# t6713_v_1_0.net
KiCad netlist of a schematic drawn in EAGLE
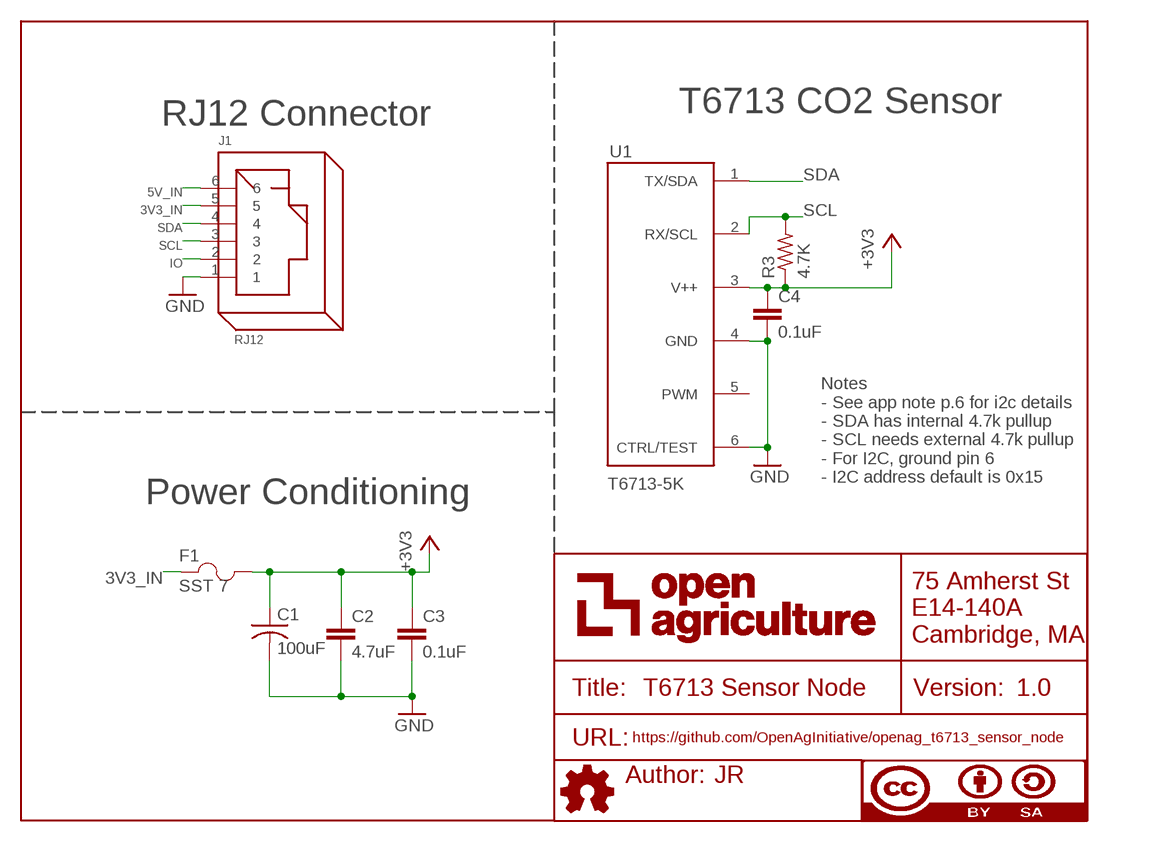
[diagram p0: schematic, sheet 1]

(export (version "E")
  (design (tool "Eeschema 10.0.6"))
  (components
    (comp (ref "C1")
      (value "100uF")
      (footprint "eagle-import:EEE-1HA101UP")
      (libsource (lib "eagle-import") (part "100UF-EEE-1HA101UP"))
    )
    (comp (ref "C2")
      (value "4.7uF")
      (footprint "eagle-import:C0805")
      (libsource (lib "eagle-import") (part "4.7UF-CL21A475KBQNNNE"))
    )
    (comp (ref "C3")
      (value "0.1uF")
      (footprint "eagle-import:C0603")
      (libsource (lib "eagle-import") (part "0.1UF-C0603C104K5RACTU"))
    )
    (comp (ref "C4")
      (value "0.1uF")
      (footprint "eagle-import:C0603")
      (libsource (lib "eagle-import") (part "0.1UF-C0603C104K5RACTU"))
    )
    (comp (ref "F1")
      (value "SST 7")
      (footprint "eagle-import:SS")
      (libsource (lib "eagle-import") (part "SST_7"))
    )
    (comp (ref "FRAME1")
      (value "DOCFIELD")
      (footprint "eagle-import:DOCFIELD")
      (fields
        (field (name "AUTHOR") "JR")
        (field (name "TITLE") "T6713 Sensor Node")
        (field (name "URL") "https://github.com/OpenAgInitiative/openag_t6713_sensor_node")
      )
      (libsource (lib "eagle-import") (part "DOCFIELD"))
    )
    (comp (ref "J1")
      (value "RJ12")
      (footprint "eagle-import:RJ12")
      (libsource (lib "eagle-import") (part "A-2004-1-4-LP-N-R"))
    )
    (comp (ref "R3")
      (value "4.7K")
      (footprint "eagle-import:R1206")
      (libsource (lib "eagle-import") (part "4.7K-RC1206JR-074K7L"))
    )
    (comp (ref "U1")
      (value "T6713-5K")
      (footprint "eagle-import:T6713")
      (libsource (lib "eagle-import") (part "T6713-5K"))
    )
  )
  (nets
    (net (code "1") (name "+3V3") (class "Default")
      (node (ref "C1") (pin "+") (pinfunction "1(+)_+") (pintype "passive"))
      (node (ref "C2") (pin "1") (pinfunction "1_1") (pintype "passive"))
      (node (ref "C3") (pin "1") (pinfunction "1_1") (pintype "passive"))
      (node (ref "C4") (pin "1") (pinfunction "1_1") (pintype "passive"))
      (node (ref "F1") (pin "2") (pinfunction "2_2") (pintype "passive"))
      (node (ref "R3") (pin "1") (pinfunction "1_1") (pintype "passive"))
      (node (ref "U1") (pin "3") (pinfunction "V++_3") (pintype "power_in"))
    )
    (net (code "2") (name "3V3_IN") (class "Default")
      (node (ref "F1") (pin "1") (pinfunction "1_1") (pintype "passive"))
      (node (ref "J1") (pin "5") (pinfunction "5_5") (pintype "bidirectional"))
    )
    (net (code "3") (name "5V_IN") (class "Default")
      (node (ref "J1") (pin "6") (pinfunction "6_6") (pintype "bidirectional"))
    )
    (net (code "4") (name "GND") (class "Default")
      (node (ref "C1") (pin "-") (pinfunction "2(-)_-") (pintype "passive"))
      (node (ref "C2") (pin "2") (pinfunction "2_2") (pintype "passive"))
      (node (ref "C3") (pin "2") (pinfunction "2_2") (pintype "passive"))
      (node (ref "C4") (pin "2") (pinfunction "2_2") (pintype "passive"))
      (node (ref "J1") (pin "1") (pinfunction "1_1") (pintype "bidirectional"))
      (node (ref "U1") (pin "4") (pinfunction "GND_4") (pintype "power_in"))
      (node (ref "U1") (pin "6") (pinfunction "CTRL/TEST_6") (pintype "bidirectional"))
    )
    (net (code "5") (name "IO") (class "Default")
      (node (ref "J1") (pin "2") (pinfunction "2_2") (pintype "bidirectional"))
    )
    (net (code "6") (name "SCL") (class "Default")
      (node (ref "J1") (pin "3") (pinfunction "3_3") (pintype "bidirectional"))
      (node (ref "R3") (pin "2") (pinfunction "2_2") (pintype "passive"))
      (node (ref "U1") (pin "2") (pinfunction "RX/SCL_2") (pintype "bidirectional"))
    )
    (net (code "7") (name "SDA") (class "Default")
      (node (ref "J1") (pin "4") (pinfunction "4_4") (pintype "bidirectional"))
      (node (ref "U1") (pin "1") (pinfunction "TX/SDA_1") (pintype "bidirectional"))
    )
    (net (code "8") (name "unconnected-(U1-PWM-Pad5)") (class "Default")
      (node (ref "U1") (pin "5") (pinfunction "PWM_5") (pintype "bidirectional"))
    )
  )
)
